# MSX_Paddle_Revisited.net
KiCad netlist of a schematic drawn in EAGLE
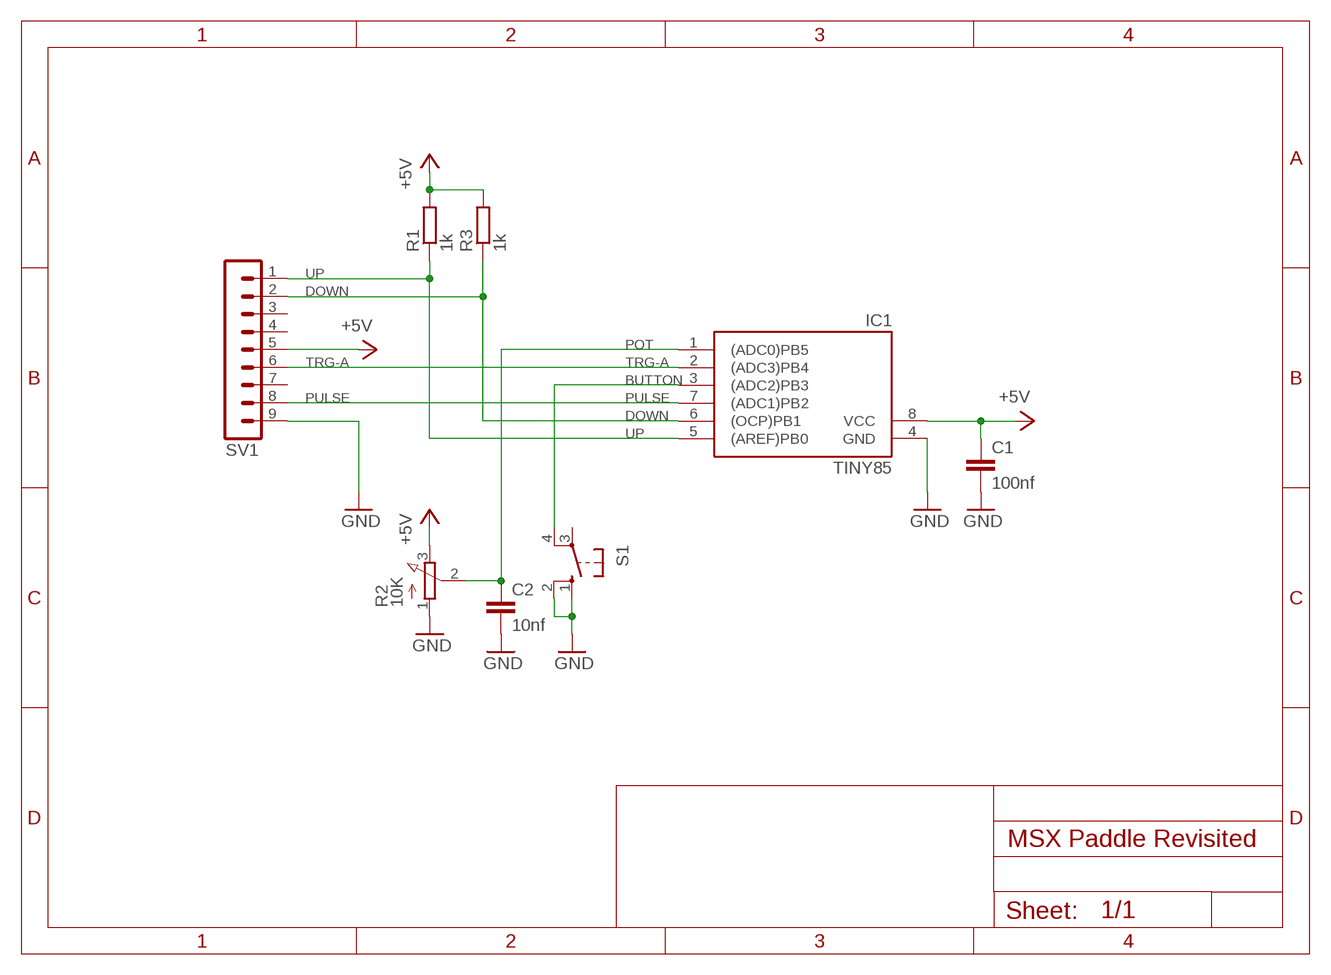
[diagram p0: schematic, sheet 1]

(export (version "E")
  (design (tool "Eeschema 10.0.6"))
  (components
    (comp (ref "C1")
      (value "100nf")
      (footprint "eagle-import:C050-024X044")
      (libsource (lib "eagle-import") (part "C-EU050-024X044"))
    )
    (comp (ref "C2")
      (value "10nf")
      (footprint "eagle-import:C050-024X044")
      (libsource (lib "eagle-import") (part "C-EU050-024X044"))
    )
    (comp (ref "IC1")
      (value "TINY85")
      (footprint "eagle-import:DIL08")
      (libsource (lib "eagle-import") (part "TINY15LP"))
    )
    (comp (ref "R1")
      (value "1k")
      (footprint "eagle-import:0204_7")
      (libsource (lib "eagle-import") (part "R-EU_0204/7"))
    )
    (comp (ref "R2")
      (value "10K")
      (footprint "eagle-import:3RP_1610N_THRU")
      (libsource (lib "eagle-import") (part "3RP/1610NTHRU"))
    )
    (comp (ref "R3")
      (value "1k")
      (footprint "eagle-import:0204_7")
      (libsource (lib "eagle-import") (part "R-EU_0204/7"))
    )
    (comp (ref "S1")
      (value "40-XX")
      (footprint "eagle-import:B3F-40XX")
      (libsource (lib "eagle-import") (part "40-XX"))
    )
    (comp (ref "SV1")
      (value "MA09-1")
      (footprint "eagle-import:MA09-1")
      (libsource (lib "eagle-import") (part "MA09-1"))
    )
  )
  (nets
    (net (code "1") (name "+5V") (class "Default")
      (node (ref "C1") (pin "1") (pinfunction "1_1") (pintype "passive"))
      (node (ref "IC1") (pin "8") (pinfunction "VCC_8") (pintype "power_in"))
      (node (ref "R1") (pin "2") (pinfunction "2_2") (pintype "passive"))
      (node (ref "R2") (pin "3") (pinfunction "E_3") (pintype "passive"))
      (node (ref "R3") (pin "2") (pinfunction "2_2") (pintype "passive"))
      (node (ref "SV1") (pin "5") (pinfunction "5_5") (pintype "passive"))
    )
    (net (code "2") (name "/BUTTON") (class "Default")
      (node (ref "IC1") (pin "3") (pinfunction "(ADC2)PB3_3") (pintype "bidirectional"))
      (node (ref "S1") (pin "4") (pinfunction "P1_4") (pintype "passive"))
    )
    (net (code "3") (name "/DOWN") (class "Default")
      (node (ref "IC1") (pin "6") (pinfunction "(OCP)PB1_6") (pintype "bidirectional"))
      (node (ref "R3") (pin "1") (pinfunction "1_1") (pintype "passive"))
      (node (ref "SV1") (pin "2") (pinfunction "2_2") (pintype "passive"))
    )
    (net (code "4") (name "/POT") (class "Default")
      (node (ref "C2") (pin "1") (pinfunction "1_1") (pintype "passive"))
      (node (ref "IC1") (pin "1") (pinfunction "(ADC0)PB5_1") (pintype "bidirectional"))
      (node (ref "R2") (pin "2") (pinfunction "S_2") (pintype "passive"))
    )
    (net (code "5") (name "/PULSE") (class "Default")
      (node (ref "IC1") (pin "7") (pinfunction "(ADC1)PB2_7") (pintype "bidirectional"))
      (node (ref "SV1") (pin "8") (pinfunction "8_8") (pintype "passive"))
    )
    (net (code "6") (name "/TRG-A") (class "Default")
      (node (ref "IC1") (pin "2") (pinfunction "(ADC3)PB4_2") (pintype "bidirectional"))
      (node (ref "SV1") (pin "6") (pinfunction "6_6") (pintype "passive"))
    )
    (net (code "7") (name "/UP") (class "Default")
      (node (ref "IC1") (pin "5") (pinfunction "(AREF)PB0_5") (pintype "bidirectional"))
      (node (ref "R1") (pin "1") (pinfunction "1_1") (pintype "passive"))
      (node (ref "SV1") (pin "1") (pinfunction "1_1") (pintype "passive"))
    )
    (net (code "8") (name "GND") (class "Default")
      (node (ref "C1") (pin "2") (pinfunction "2_2") (pintype "passive"))
      (node (ref "C2") (pin "2") (pinfunction "2_2") (pintype "passive"))
      (node (ref "IC1") (pin "4") (pinfunction "GND_4") (pintype "power_in"))
      (node (ref "R2") (pin "1") (pinfunction "A_1") (pintype "passive"))
      (node (ref "S1") (pin "1") (pinfunction "S_1") (pintype "passive"))
      (node (ref "S1") (pin "2") (pinfunction "S1_2") (pintype "passive"))
      (node (ref "SV1") (pin "9") (pinfunction "9_9") (pintype "passive"))
    )
    (net (code "9") (name "unconnected-(S1-P-Pad3)") (class "Default")
      (node (ref "S1") (pin "3") (pinfunction "P_3") (pintype "passive"))
    )
    (net (code "10") (name "unconnected-(SV1-Pad3)") (class "Default")
      (node (ref "SV1") (pin "3") (pinfunction "3_3") (pintype "passive"))
    )
    (net (code "11") (name "unconnected-(SV1-Pad4)") (class "Default")
      (node (ref "SV1") (pin "4") (pinfunction "4_4") (pintype "passive"))
    )
    (net (code "12") (name "unconnected-(SV1-Pad7)") (class "Default")
      (node (ref "SV1") (pin "7") (pinfunction "7_7") (pintype "passive"))
    )
  )
)
